# Board.net
KiCad netlist of a schematic drawn in EAGLE
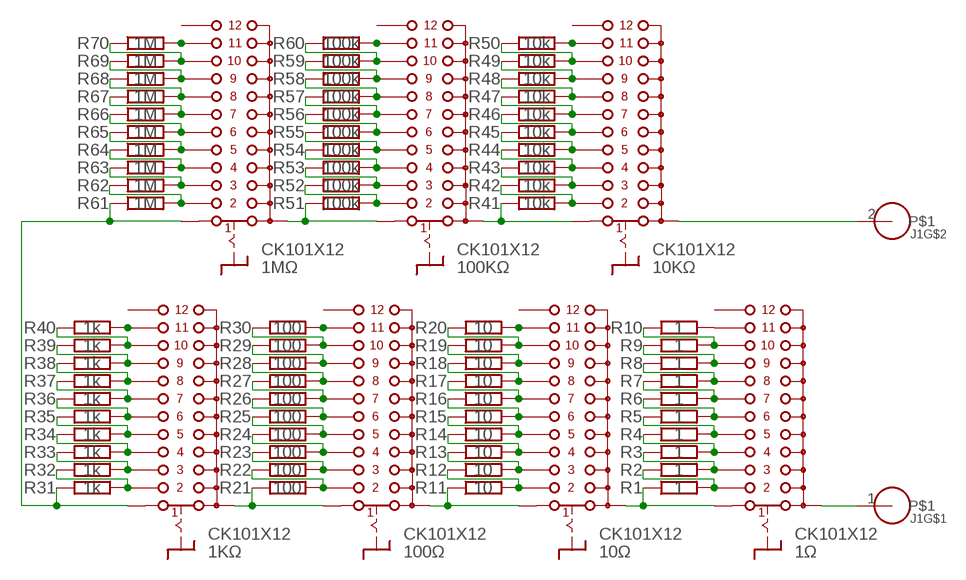
[diagram p0: schematic, sheet 1]

(export (version "E")
  (design (tool "Eeschema 10.0.6"))
  (components
    (comp (ref "1KΩ")
      (value "CK101X12")
      (footprint "eagle-import:CK101X12")
      (libsource (lib "eagle-import") (part "CK101X12"))
    )
    (comp (ref "1MΩ")
      (value "CK101X12")
      (footprint "eagle-import:CK101X12")
      (libsource (lib "eagle-import") (part "CK101X12"))
    )
    (comp (ref "1Ω")
      (value "CK101X12")
      (footprint "eagle-import:CK101X12")
      (libsource (lib "eagle-import") (part "CK101X12"))
    )
    (comp (ref "10KΩ")
      (value "CK101X12")
      (footprint "eagle-import:CK101X12")
      (libsource (lib "eagle-import") (part "CK101X12"))
    )
    (comp (ref "10Ω")
      (value "CK101X12")
      (footprint "eagle-import:CK101X12")
      (libsource (lib "eagle-import") (part "CK101X12"))
    )
    (comp (ref "100KΩ")
      (value "CK101X12")
      (footprint "eagle-import:CK101X12")
      (libsource (lib "eagle-import") (part "CK101X12"))
    )
    (comp (ref "100Ω")
      (value "CK101X12")
      (footprint "eagle-import:CK101X12")
      (libsource (lib "eagle-import") (part "CK101X12"))
    )
    (comp (ref "J1")
      (value "MOLEX-1X2")
      (footprint "eagle-import:MOLEX-1X2_LOCK")
      (libsource (lib "eagle-import") (part "MOLEX-1X2"))
    )
    (comp (ref "R1")
      (value "1")
      (footprint "eagle-import:0207_2V")
      (libsource (lib "eagle-import") (part "R-EU"))
    )
    (comp (ref "R2")
      (value "1")
      (footprint "eagle-import:0207_2V")
      (libsource (lib "eagle-import") (part "R-EU"))
    )
    (comp (ref "R3")
      (value "1")
      (footprint "eagle-import:0207_2V")
      (libsource (lib "eagle-import") (part "R-EU"))
    )
    (comp (ref "R4")
      (value "1")
      (footprint "eagle-import:0207_2V")
      (libsource (lib "eagle-import") (part "R-EU"))
    )
    (comp (ref "R5")
      (value "1")
      (footprint "eagle-import:0207_2V")
      (libsource (lib "eagle-import") (part "R-EU"))
    )
    (comp (ref "R6")
      (value "1")
      (footprint "eagle-import:0207_2V")
      (libsource (lib "eagle-import") (part "R-EU"))
    )
    (comp (ref "R7")
      (value "1")
      (footprint "eagle-import:0207_2V")
      (libsource (lib "eagle-import") (part "R-EU"))
    )
    (comp (ref "R8")
      (value "1")
      (footprint "eagle-import:0207_2V")
      (libsource (lib "eagle-import") (part "R-EU"))
    )
    (comp (ref "R9")
      (value "1")
      (footprint "eagle-import:0207_2V")
      (libsource (lib "eagle-import") (part "R-EU"))
    )
    (comp (ref "R10")
      (value "1")
      (footprint "eagle-import:0207_2V")
      (libsource (lib "eagle-import") (part "R-EU"))
    )
    (comp (ref "R11")
      (value "10")
      (footprint "eagle-import:0207_2V")
      (libsource (lib "eagle-import") (part "R-EU"))
    )
    (comp (ref "R12")
      (value "10")
      (footprint "eagle-import:0207_2V")
      (libsource (lib "eagle-import") (part "R-EU"))
    )
    (comp (ref "R13")
      (value "10")
      (footprint "eagle-import:0207_2V")
      (libsource (lib "eagle-import") (part "R-EU"))
    )
    (comp (ref "R14")
      (value "10")
      (footprint "eagle-import:0207_2V")
      (libsource (lib "eagle-import") (part "R-EU"))
    )
    (comp (ref "R15")
      (value "10")
      (footprint "eagle-import:0207_2V")
      (libsource (lib "eagle-import") (part "R-EU"))
    )
    (comp (ref "R16")
      (value "10")
      (footprint "eagle-import:0207_2V")
      (libsource (lib "eagle-import") (part "R-EU"))
    )
    (comp (ref "R17")
      (value "10")
      (footprint "eagle-import:0207_2V")
      (libsource (lib "eagle-import") (part "R-EU"))
    )
    (comp (ref "R18")
      (value "10")
      (footprint "eagle-import:0207_2V")
      (libsource (lib "eagle-import") (part "R-EU"))
    )
    (comp (ref "R19")
      (value "10")
      (footprint "eagle-import:0207_2V")
      (libsource (lib "eagle-import") (part "R-EU"))
    )
    (comp (ref "R20")
      (value "10")
      (footprint "eagle-import:0207_2V")
      (libsource (lib "eagle-import") (part "R-EU"))
    )
    (comp (ref "R21")
      (value "100")
      (footprint "eagle-import:0207_2V")
      (libsource (lib "eagle-import") (part "R-EU"))
    )
    (comp (ref "R22")
      (value "100")
      (footprint "eagle-import:0207_2V")
      (libsource (lib "eagle-import") (part "R-EU"))
    )
    (comp (ref "R23")
      (value "100")
      (footprint "eagle-import:0207_2V")
      (libsource (lib "eagle-import") (part "R-EU"))
    )
    (comp (ref "R24")
      (value "100")
      (footprint "eagle-import:0207_2V")
      (libsource (lib "eagle-import") (part "R-EU"))
    )
    (comp (ref "R25")
      (value "100")
      (footprint "eagle-import:0207_2V")
      (libsource (lib "eagle-import") (part "R-EU"))
    )
    (comp (ref "R26")
      (value "100")
      (footprint "eagle-import:0207_2V")
      (libsource (lib "eagle-import") (part "R-EU"))
    )
    (comp (ref "R27")
      (value "100")
      (footprint "eagle-import:0207_2V")
      (libsource (lib "eagle-import") (part "R-EU"))
    )
    (comp (ref "R28")
      (value "100")
      (footprint "eagle-import:0207_2V")
      (libsource (lib "eagle-import") (part "R-EU"))
    )
    (comp (ref "R29")
      (value "100")
      (footprint "eagle-import:0207_2V")
      (libsource (lib "eagle-import") (part "R-EU"))
    )
    (comp (ref "R30")
      (value "100")
      (footprint "eagle-import:0207_2V")
      (libsource (lib "eagle-import") (part "R-EU"))
    )
    (comp (ref "R31")
      (value "1k")
      (footprint "eagle-import:0207_2V")
      (libsource (lib "eagle-import") (part "R-EU"))
    )
    (comp (ref "R32")
      (value "1k")
      (footprint "eagle-import:0207_2V")
      (libsource (lib "eagle-import") (part "R-EU"))
    )
    (comp (ref "R33")
      (value "1k")
      (footprint "eagle-import:0207_2V")
      (libsource (lib "eagle-import") (part "R-EU"))
    )
    (comp (ref "R34")
      (value "1k")
      (footprint "eagle-import:0207_2V")
      (libsource (lib "eagle-import") (part "R-EU"))
    )
    (comp (ref "R35")
      (value "1k")
      (footprint "eagle-import:0207_2V")
      (libsource (lib "eagle-import") (part "R-EU"))
    )
    (comp (ref "R36")
      (value "1k")
      (footprint "eagle-import:0207_2V")
      (libsource (lib "eagle-import") (part "R-EU"))
    )
    (comp (ref "R37")
      (value "1k")
      (footprint "eagle-import:0207_2V")
      (libsource (lib "eagle-import") (part "R-EU"))
    )
    (comp (ref "R38")
      (value "1k")
      (footprint "eagle-import:0207_2V")
      (libsource (lib "eagle-import") (part "R-EU"))
    )
    (comp (ref "R39")
      (value "1k")
      (footprint "eagle-import:0207_2V")
      (libsource (lib "eagle-import") (part "R-EU"))
    )
    (comp (ref "R40")
      (value "1k")
      (footprint "eagle-import:0207_2V")
      (libsource (lib "eagle-import") (part "R-EU"))
    )
    (comp (ref "R41")
      (value "10k")
      (footprint "eagle-import:0207_2V")
      (libsource (lib "eagle-import") (part "R-EU"))
    )
    (comp (ref "R42")
      (value "10k")
      (footprint "eagle-import:0207_2V")
      (libsource (lib "eagle-import") (part "R-EU"))
    )
    (comp (ref "R43")
      (value "10k")
      (footprint "eagle-import:0207_2V")
      (libsource (lib "eagle-import") (part "R-EU"))
    )
    (comp (ref "R44")
      (value "10k")
      (footprint "eagle-import:0207_2V")
      (libsource (lib "eagle-import") (part "R-EU"))
    )
    (comp (ref "R45")
      (value "10k")
      (footprint "eagle-import:0207_2V")
      (libsource (lib "eagle-import") (part "R-EU"))
    )
    (comp (ref "R46")
      (value "10k")
      (footprint "eagle-import:0207_2V")
      (libsource (lib "eagle-import") (part "R-EU"))
    )
    (comp (ref "R47")
      (value "10k")
      (footprint "eagle-import:0207_2V")
      (libsource (lib "eagle-import") (part "R-EU"))
    )
    (comp (ref "R48")
      (value "10k")
      (footprint "eagle-import:0207_2V")
      (libsource (lib "eagle-import") (part "R-EU"))
    )
    (comp (ref "R49")
      (value "10k")
      (footprint "eagle-import:0207_2V")
      (libsource (lib "eagle-import") (part "R-EU"))
    )
    (comp (ref "R50")
      (value "10k")
      (footprint "eagle-import:0207_2V")
      (libsource (lib "eagle-import") (part "R-EU"))
    )
    (comp (ref "R51")
      (value "100k")
      (footprint "eagle-import:0207_2V")
      (libsource (lib "eagle-import") (part "R-EU"))
    )
    (comp (ref "R52")
      (value "100k")
      (footprint "eagle-import:0207_2V")
      (libsource (lib "eagle-import") (part "R-EU"))
    )
    (comp (ref "R53")
      (value "100k")
      (footprint "eagle-import:0207_2V")
      (libsource (lib "eagle-import") (part "R-EU"))
    )
    (comp (ref "R54")
      (value "100k")
      (footprint "eagle-import:0207_2V")
      (libsource (lib "eagle-import") (part "R-EU"))
    )
    (comp (ref "R55")
      (value "100k")
      (footprint "eagle-import:0207_2V")
      (libsource (lib "eagle-import") (part "R-EU"))
    )
    (comp (ref "R56")
      (value "100k")
      (footprint "eagle-import:0207_2V")
      (libsource (lib "eagle-import") (part "R-EU"))
    )
    (comp (ref "R57")
      (value "100k")
      (footprint "eagle-import:0207_2V")
      (libsource (lib "eagle-import") (part "R-EU"))
    )
    (comp (ref "R58")
      (value "100k")
      (footprint "eagle-import:0207_2V")
      (libsource (lib "eagle-import") (part "R-EU"))
    )
    (comp (ref "R59")
      (value "100k")
      (footprint "eagle-import:0207_2V")
      (libsource (lib "eagle-import") (part "R-EU"))
    )
    (comp (ref "R60")
      (value "100k")
      (footprint "eagle-import:0207_2V")
      (libsource (lib "eagle-import") (part "R-EU"))
    )
    (comp (ref "R61")
      (value "1M")
      (footprint "eagle-import:0207_2V")
      (libsource (lib "eagle-import") (part "R-EU"))
    )
    (comp (ref "R62")
      (value "1M")
      (footprint "eagle-import:0207_2V")
      (libsource (lib "eagle-import") (part "R-EU"))
    )
    (comp (ref "R63")
      (value "1M")
      (footprint "eagle-import:0207_2V")
      (libsource (lib "eagle-import") (part "R-EU"))
    )
    (comp (ref "R64")
      (value "1M")
      (footprint "eagle-import:0207_2V")
      (libsource (lib "eagle-import") (part "R-EU"))
    )
    (comp (ref "R65")
      (value "1M")
      (footprint "eagle-import:0207_2V")
      (libsource (lib "eagle-import") (part "R-EU"))
    )
    (comp (ref "R66")
      (value "1M")
      (footprint "eagle-import:0207_2V")
      (libsource (lib "eagle-import") (part "R-EU"))
    )
    (comp (ref "R67")
      (value "1M")
      (footprint "eagle-import:0207_2V")
      (libsource (lib "eagle-import") (part "R-EU"))
    )
    (comp (ref "R68")
      (value "1M")
      (footprint "eagle-import:0207_2V")
      (libsource (lib "eagle-import") (part "R-EU"))
    )
    (comp (ref "R69")
      (value "1M")
      (footprint "eagle-import:0207_2V")
      (libsource (lib "eagle-import") (part "R-EU"))
    )
    (comp (ref "R70")
      (value "1M")
      (footprint "eagle-import:0207_2V")
      (libsource (lib "eagle-import") (part "R-EU"))
    )
  )
  (nets
    (net (code "1") (name "Net-(1KΩ-Pad1)") (class "Default")
      (node (ref "1KΩ") (pin "1") (pinfunction "1_1") (pintype "passive"))
      (node (ref "1MΩ") (pin "1") (pinfunction "1_1") (pintype "passive"))
      (node (ref "R31") (pin "1") (pinfunction "1_1") (pintype "passive"))
      (node (ref "R61") (pin "1") (pinfunction "1_1") (pintype "passive"))
    )
    (net (code "2") (name "Net-(1KΩ-Pad2)") (class "Default")
      (node (ref "1KΩ") (pin "2") (pinfunction "2_2") (pintype "passive"))
      (node (ref "R31") (pin "2") (pinfunction "2_2") (pintype "passive"))
      (node (ref "R32") (pin "1") (pinfunction "1_1") (pintype "passive"))
    )
    (net (code "3") (name "Net-(1KΩ-Pad3)") (class "Default")
      (node (ref "1KΩ") (pin "3") (pinfunction "3_3") (pintype "passive"))
      (node (ref "R32") (pin "2") (pinfunction "2_2") (pintype "passive"))
      (node (ref "R33") (pin "1") (pinfunction "1_1") (pintype "passive"))
    )
    (net (code "4") (name "Net-(1KΩ-Pad4)") (class "Default")
      (node (ref "1KΩ") (pin "4") (pinfunction "4_4") (pintype "passive"))
      (node (ref "R33") (pin "2") (pinfunction "2_2") (pintype "passive"))
      (node (ref "R34") (pin "1") (pinfunction "1_1") (pintype "passive"))
    )
    (net (code "5") (name "Net-(1KΩ-Pad5)") (class "Default")
      (node (ref "1KΩ") (pin "5") (pinfunction "5_5") (pintype "passive"))
      (node (ref "R34") (pin "2") (pinfunction "2_2") (pintype "passive"))
      (node (ref "R35") (pin "1") (pinfunction "1_1") (pintype "passive"))
    )
    (net (code "6") (name "Net-(1KΩ-Pad6)") (class "Default")
      (node (ref "1KΩ") (pin "6") (pinfunction "6_6") (pintype "passive"))
      (node (ref "R35") (pin "2") (pinfunction "2_2") (pintype "passive"))
      (node (ref "R36") (pin "1") (pinfunction "1_1") (pintype "passive"))
    )
    (net (code "7") (name "Net-(1KΩ-Pad7)") (class "Default")
      (node (ref "1KΩ") (pin "7") (pinfunction "7_7") (pintype "passive"))
      (node (ref "R36") (pin "2") (pinfunction "2_2") (pintype "passive"))
      (node (ref "R37") (pin "1") (pinfunction "1_1") (pintype "passive"))
    )
    (net (code "8") (name "Net-(1KΩ-Pad8)") (class "Default")
      (node (ref "1KΩ") (pin "8") (pinfunction "8_8") (pintype "passive"))
      (node (ref "R37") (pin "2") (pinfunction "2_2") (pintype "passive"))
      (node (ref "R38") (pin "1") (pinfunction "1_1") (pintype "passive"))
    )
    (net (code "9") (name "Net-(1KΩ-Pad9)") (class "Default")
      (node (ref "1KΩ") (pin "9") (pinfunction "9_9") (pintype "passive"))
      (node (ref "R38") (pin "2") (pinfunction "2_2") (pintype "passive"))
      (node (ref "R39") (pin "1") (pinfunction "1_1") (pintype "passive"))
    )
    (net (code "10") (name "Net-(1KΩ-Pad10)") (class "Default")
      (node (ref "1KΩ") (pin "10") (pinfunction "10_10") (pintype "passive"))
      (node (ref "R39") (pin "2") (pinfunction "2_2") (pintype "passive"))
      (node (ref "R40") (pin "1") (pinfunction "1_1") (pintype "passive"))
    )
    (net (code "11") (name "Net-(1KΩ-Pad11)") (class "Default")
      (node (ref "1KΩ") (pin "11") (pinfunction "11_11") (pintype "passive"))
      (node (ref "R40") (pin "2") (pinfunction "2_2") (pintype "passive"))
    )
    (net (code "12") (name "Net-(1MΩ-Pad2)") (class "Default")
      (node (ref "1MΩ") (pin "2") (pinfunction "2_2") (pintype "passive"))
      (node (ref "R61") (pin "2") (pinfunction "2_2") (pintype "passive"))
      (node (ref "R62") (pin "1") (pinfunction "1_1") (pintype "passive"))
    )
    (net (code "13") (name "Net-(1MΩ-Pad3)") (class "Default")
      (node (ref "1MΩ") (pin "3") (pinfunction "3_3") (pintype "passive"))
      (node (ref "R62") (pin "2") (pinfunction "2_2") (pintype "passive"))
      (node (ref "R63") (pin "1") (pinfunction "1_1") (pintype "passive"))
    )
    (net (code "14") (name "Net-(1MΩ-Pad4)") (class "Default")
      (node (ref "1MΩ") (pin "4") (pinfunction "4_4") (pintype "passive"))
      (node (ref "R63") (pin "2") (pinfunction "2_2") (pintype "passive"))
      (node (ref "R64") (pin "1") (pinfunction "1_1") (pintype "passive"))
    )
    (net (code "15") (name "Net-(1MΩ-Pad5)") (class "Default")
      (node (ref "1MΩ") (pin "5") (pinfunction "5_5") (pintype "passive"))
      (node (ref "R64") (pin "2") (pinfunction "2_2") (pintype "passive"))
      (node (ref "R65") (pin "1") (pinfunction "1_1") (pintype "passive"))
    )
    (net (code "16") (name "Net-(1MΩ-Pad6)") (class "Default")
      (node (ref "1MΩ") (pin "6") (pinfunction "6_6") (pintype "passive"))
      (node (ref "R65") (pin "2") (pinfunction "2_2") (pintype "passive"))
      (node (ref "R66") (pin "1") (pinfunction "1_1") (pintype "passive"))
    )
    (net (code "17") (name "Net-(1MΩ-Pad7)") (class "Default")
      (node (ref "1MΩ") (pin "7") (pinfunction "7_7") (pintype "passive"))
      (node (ref "R66") (pin "2") (pinfunction "2_2") (pintype "passive"))
      (node (ref "R67") (pin "1") (pinfunction "1_1") (pintype "passive"))
    )
    (net (code "18") (name "Net-(1MΩ-Pad8)") (class "Default")
      (node (ref "1MΩ") (pin "8") (pinfunction "8_8") (pintype "passive"))
      (node (ref "R67") (pin "2") (pinfunction "2_2") (pintype "passive"))
      (node (ref "R68") (pin "1") (pinfunction "1_1") (pintype "passive"))
    )
    (net (code "19") (name "Net-(1MΩ-Pad9)") (class "Default")
      (node (ref "1MΩ") (pin "9") (pinfunction "9_9") (pintype "passive"))
      (node (ref "R68") (pin "2") (pinfunction "2_2") (pintype "passive"))
      (node (ref "R69") (pin "1") (pinfunction "1_1") (pintype "passive"))
    )
    (net (code "20") (name "Net-(1MΩ-Pad10)") (class "Default")
      (node (ref "1MΩ") (pin "10") (pinfunction "10_10") (pintype "passive"))
      (node (ref "R69") (pin "2") (pinfunction "2_2") (pintype "passive"))
      (node (ref "R70") (pin "1") (pinfunction "1_1") (pintype "passive"))
    )
    (net (code "21") (name "Net-(1MΩ-Pad11)") (class "Default")
      (node (ref "1MΩ") (pin "11") (pinfunction "11_11") (pintype "passive"))
      (node (ref "R70") (pin "2") (pinfunction "2_2") (pintype "passive"))
    )
    (net (code "22") (name "Net-(1Ω-Pad2)") (class "Default")
      (node (ref "1Ω") (pin "2") (pinfunction "2_2") (pintype "passive"))
      (node (ref "R1") (pin "2") (pinfunction "2_2") (pintype "passive"))
      (node (ref "R2") (pin "1") (pinfunction "1_1") (pintype "passive"))
    )
    (net (code "23") (name "Net-(1Ω-Pad3)") (class "Default")
      (node (ref "1Ω") (pin "3") (pinfunction "3_3") (pintype "passive"))
      (node (ref "R2") (pin "2") (pinfunction "2_2") (pintype "passive"))
      (node (ref "R3") (pin "1") (pinfunction "1_1") (pintype "passive"))
    )
    (net (code "24") (name "Net-(1Ω-Pad4)") (class "Default")
      (node (ref "1Ω") (pin "4") (pinfunction "4_4") (pintype "passive"))
      (node (ref "R3") (pin "2") (pinfunction "2_2") (pintype "passive"))
      (node (ref "R4") (pin "1") (pinfunction "1_1") (pintype "passive"))
    )
    (net (code "25") (name "Net-(1Ω-Pad5)") (class "Default")
      (node (ref "1Ω") (pin "5") (pinfunction "5_5") (pintype "passive"))
      (node (ref "R4") (pin "2") (pinfunction "2_2") (pintype "passive"))
      (node (ref "R5") (pin "1") (pinfunction "1_1") (pintype "passive"))
    )
    (net (code "26") (name "Net-(1Ω-Pad6)") (class "Default")
      (node (ref "1Ω") (pin "6") (pinfunction "6_6") (pintype "passive"))
      (node (ref "R5") (pin "2") (pinfunction "2_2") (pintype "passive"))
      (node (ref "R6") (pin "1") (pinfunction "1_1") (pintype "passive"))
    )
    (net (code "27") (name "Net-(1Ω-Pad7)") (class "Default")
      (node (ref "1Ω") (pin "7") (pinfunction "7_7") (pintype "passive"))
      (node (ref "R6") (pin "2") (pinfunction "2_2") (pintype "passive"))
      (node (ref "R7") (pin "1") (pinfunction "1_1") (pintype "passive"))
    )
    (net (code "28") (name "Net-(1Ω-Pad8)") (class "Default")
      (node (ref "1Ω") (pin "8") (pinfunction "8_8") (pintype "passive"))
      (node (ref "R7") (pin "2") (pinfunction "2_2") (pintype "passive"))
      (node (ref "R8") (pin "1") (pinfunction "1_1") (pintype "passive"))
    )
    (net (code "29") (name "Net-(1Ω-Pad9)") (class "Default")
      (node (ref "1Ω") (pin "9") (pinfunction "9_9") (pintype "passive"))
      (node (ref "R8") (pin "2") (pinfunction "2_2") (pintype "passive"))
      (node (ref "R9") (pin "1") (pinfunction "1_1") (pintype "passive"))
    )
    (net (code "30") (name "Net-(1Ω-Pad10)") (class "Default")
      (node (ref "1Ω") (pin "10") (pinfunction "10_10") (pintype "passive"))
      (node (ref "R10") (pin "1") (pinfunction "1_1") (pintype "passive"))
      (node (ref "R9") (pin "2") (pinfunction "2_2") (pintype "passive"))
    )
    (net (code "31") (name "Net-(1Ω-Pad11)") (class "Default")
      (node (ref "1Ω") (pin "11") (pinfunction "11_11") (pintype "passive"))
      (node (ref "R10") (pin "2") (pinfunction "2_2") (pintype "passive"))
    )
    (net (code "32") (name "Net-(10KΩ-Pad2)") (class "Default")
      (node (ref "10KΩ") (pin "2") (pinfunction "2_2") (pintype "passive"))
      (node (ref "R41") (pin "2") (pinfunction "2_2") (pintype "passive"))
      (node (ref "R42") (pin "1") (pinfunction "1_1") (pintype "passive"))
    )
    (net (code "33") (name "Net-(10KΩ-Pad3)") (class "Default")
      (node (ref "10KΩ") (pin "3") (pinfunction "3_3") (pintype "passive"))
      (node (ref "R42") (pin "2") (pinfunction "2_2") (pintype "passive"))
      (node (ref "R43") (pin "1") (pinfunction "1_1") (pintype "passive"))
    )
    (net (code "34") (name "Net-(10KΩ-Pad4)") (class "Default")
      (node (ref "10KΩ") (pin "4") (pinfunction "4_4") (pintype "passive"))
      (node (ref "R43") (pin "2") (pinfunction "2_2") (pintype "passive"))
      (node (ref "R44") (pin "1") (pinfunction "1_1") (pintype "passive"))
    )
    (net (code "35") (name "Net-(10KΩ-Pad5)") (class "Default")
      (node (ref "10KΩ") (pin "5") (pinfunction "5_5") (pintype "passive"))
      (node (ref "R44") (pin "2") (pinfunction "2_2") (pintype "passive"))
      (node (ref "R45") (pin "1") (pinfunction "1_1") (pintype "passive"))
    )
    (net (code "36") (name "Net-(10KΩ-Pad6)") (class "Default")
      (node (ref "10KΩ") (pin "6") (pinfunction "6_6") (pintype "passive"))
      (node (ref "R45") (pin "2") (pinfunction "2_2") (pintype "passive"))
      (node (ref "R46") (pin "1") (pinfunction "1_1") (pintype "passive"))
    )
    (net (code "37") (name "Net-(10KΩ-Pad7)") (class "Default")
      (node (ref "10KΩ") (pin "7") (pinfunction "7_7") (pintype "passive"))
      (node (ref "R46") (pin "2") (pinfunction "2_2") (pintype "passive"))
      (node (ref "R47") (pin "1") (pinfunction "1_1") (pintype "passive"))
    )
    (net (code "38") (name "Net-(10KΩ-Pad8)") (class "Default")
      (node (ref "10KΩ") (pin "8") (pinfunction "8_8") (pintype "passive"))
      (node (ref "R47") (pin "2") (pinfunction "2_2") (pintype "passive"))
      (node (ref "R48") (pin "1") (pinfunction "1_1") (pintype "passive"))
    )
    (net (code "39") (name "Net-(10KΩ-Pad9)") (class "Default")
      (node (ref "10KΩ") (pin "9") (pinfunction "9_9") (pintype "passive"))
      (node (ref "R48") (pin "2") (pinfunction "2_2") (pintype "passive"))
      (node (ref "R49") (pin "1") (pinfunction "1_1") (pintype "passive"))
    )
    (net (code "40") (name "Net-(10KΩ-Pad10)") (class "Default")
      (node (ref "10KΩ") (pin "10") (pinfunction "10_10") (pintype "passive"))
      (node (ref "R49") (pin "2") (pinfunction "2_2") (pintype "passive"))
      (node (ref "R50") (pin "1") (pinfunction "1_1") (pintype "passive"))
    )
    (net (code "41") (name "Net-(10KΩ-Pad11)") (class "Default")
      (node (ref "10KΩ") (pin "11") (pinfunction "11_11") (pintype "passive"))
      (node (ref "R50") (pin "2") (pinfunction "2_2") (pintype "passive"))
    )
    (net (code "42") (name "Net-(10Ω-Pad2)") (class "Default")
      (node (ref "10Ω") (pin "2") (pinfunction "2_2") (pintype "passive"))
      (node (ref "R11") (pin "2") (pinfunction "2_2") (pintype "passive"))
      (node (ref "R12") (pin "1") (pinfunction "1_1") (pintype "passive"))
    )
    (net (code "43") (name "Net-(10Ω-Pad3)") (class "Default")
      (node (ref "10Ω") (pin "3") (pinfunction "3_3") (pintype "passive"))
      (node (ref "R12") (pin "2") (pinfunction "2_2") (pintype "passive"))
      (node (ref "R13") (pin "1") (pinfunction "1_1") (pintype "passive"))
    )
    (net (code "44") (name "Net-(10Ω-Pad4)") (class "Default")
      (node (ref "10Ω") (pin "4") (pinfunction "4_4") (pintype "passive"))
      (node (ref "R13") (pin "2") (pinfunction "2_2") (pintype "passive"))
      (node (ref "R14") (pin "1") (pinfunction "1_1") (pintype "passive"))
    )
    (net (code "45") (name "Net-(10Ω-Pad5)") (class "Default")
      (node (ref "10Ω") (pin "5") (pinfunction "5_5") (pintype "passive"))
      (node (ref "R14") (pin "2") (pinfunction "2_2") (pintype "passive"))
      (node (ref "R15") (pin "1") (pinfunction "1_1") (pintype "passive"))
    )
    (net (code "46") (name "Net-(10Ω-Pad6)") (class "Default")
      (node (ref "10Ω") (pin "6") (pinfunction "6_6") (pintype "passive"))
      (node (ref "R15") (pin "2") (pinfunction "2_2") (pintype "passive"))
      (node (ref "R16") (pin "1") (pinfunction "1_1") (pintype "passive"))
    )
    (net (code "47") (name "Net-(10Ω-Pad7)") (class "Default")
      (node (ref "10Ω") (pin "7") (pinfunction "7_7") (pintype "passive"))
      (node (ref "R16") (pin "2") (pinfunction "2_2") (pintype "passive"))
      (node (ref "R17") (pin "1") (pinfunction "1_1") (pintype "passive"))
    )
    (net (code "48") (name "Net-(10Ω-Pad8)") (class "Default")
      (node (ref "10Ω") (pin "8") (pinfunction "8_8") (pintype "passive"))
      (node (ref "R17") (pin "2") (pinfunction "2_2") (pintype "passive"))
      (node (ref "R18") (pin "1") (pinfunction "1_1") (pintype "passive"))
    )
    (net (code "49") (name "Net-(10Ω-Pad9)") (class "Default")
      (node (ref "10Ω") (pin "9") (pinfunction "9_9") (pintype "passive"))
      (node (ref "R18") (pin "2") (pinfunction "2_2") (pintype "passive"))
      (node (ref "R19") (pin "1") (pinfunction "1_1") (pintype "passive"))
    )
    (net (code "50") (name "Net-(10Ω-Pad10)") (class "Default")
      (node (ref "10Ω") (pin "10") (pinfunction "10_10") (pintype "passive"))
      (node (ref "R19") (pin "2") (pinfunction "2_2") (pintype "passive"))
      (node (ref "R20") (pin "1") (pinfunction "1_1") (pintype "passive"))
    )
    (net (code "51") (name "Net-(10Ω-Pad11)") (class "Default")
      (node (ref "10Ω") (pin "11") (pinfunction "11_11") (pintype "passive"))
      (node (ref "R20") (pin "2") (pinfunction "2_2") (pintype "passive"))
    )
    (net (code "52") (name "Net-(10Ω-PadA)") (class "Default")
      (node (ref "10Ω") (pin "A") (pinfunction "A_A") (pintype "passive"))
      (node (ref "1Ω") (pin "1") (pinfunction "1_1") (pintype "passive"))
      (node (ref "R1") (pin "1") (pinfunction "1_1") (pintype "passive"))
    )
    (net (code "53") (name "Net-(100KΩ-Pad1)") (class "Default")
      (node (ref "100KΩ") (pin "1") (pinfunction "1_1") (pintype "passive"))
      (node (ref "1MΩ") (pin "A") (pinfunction "A_A") (pintype "passive"))
      (node (ref "R51") (pin "1") (pinfunction "1_1") (pintype "passive"))
    )
    (net (code "54") (name "Net-(100KΩ-Pad2)") (class "Default")
      (node (ref "100KΩ") (pin "2") (pinfunction "2_2") (pintype "passive"))
      (node (ref "R51") (pin "2") (pinfunction "2_2") (pintype "passive"))
      (node (ref "R52") (pin "1") (pinfunction "1_1") (pintype "passive"))
    )
    (net (code "55") (name "Net-(100KΩ-Pad3)") (class "Default")
      (node (ref "100KΩ") (pin "3") (pinfunction "3_3") (pintype "passive"))
      (node (ref "R52") (pin "2") (pinfunction "2_2") (pintype "passive"))
      (node (ref "R53") (pin "1") (pinfunction "1_1") (pintype "passive"))
    )
    (net (code "56") (name "Net-(100KΩ-Pad4)") (class "Default")
      (node (ref "100KΩ") (pin "4") (pinfunction "4_4") (pintype "passive"))
      (node (ref "R53") (pin "2") (pinfunction "2_2") (pintype "passive"))
      (node (ref "R54") (pin "1") (pinfunction "1_1") (pintype "passive"))
    )
    (net (code "57") (name "Net-(100KΩ-Pad5)") (class "Default")
      (node (ref "100KΩ") (pin "5") (pinfunction "5_5") (pintype "passive"))
      (node (ref "R54") (pin "2") (pinfunction "2_2") (pintype "passive"))
      (node (ref "R55") (pin "1") (pinfunction "1_1") (pintype "passive"))
    )
    (net (code "58") (name "Net-(100KΩ-Pad6)") (class "Default")
      (node (ref "100KΩ") (pin "6") (pinfunction "6_6") (pintype "passive"))
      (node (ref "R55") (pin "2") (pinfunction "2_2") (pintype "passive"))
      (node (ref "R56") (pin "1") (pinfunction "1_1") (pintype "passive"))
    )
    (net (code "59") (name "Net-(100KΩ-Pad7)") (class "Default")
      (node (ref "100KΩ") (pin "7") (pinfunction "7_7") (pintype "passive"))
      (node (ref "R56") (pin "2") (pinfunction "2_2") (pintype "passive"))
      (node (ref "R57") (pin "1") (pinfunction "1_1") (pintype "passive"))
    )
    (net (code "60") (name "Net-(100KΩ-Pad8)") (class "Default")
      (node (ref "100KΩ") (pin "8") (pinfunction "8_8") (pintype "passive"))
      (node (ref "R57") (pin "2") (pinfunction "2_2") (pintype "passive"))
      (node (ref "R58") (pin "1") (pinfunction "1_1") (pintype "passive"))
    )
    (net (code "61") (name "Net-(100KΩ-Pad9)") (class "Default")
      (node (ref "100KΩ") (pin "9") (pinfunction "9_9") (pintype "passive"))
      (node (ref "R58") (pin "2") (pinfunction "2_2") (pintype "passive"))
      (node (ref "R59") (pin "1") (pinfunction "1_1") (pintype "passive"))
    )
    (net (code "62") (name "Net-(100KΩ-Pad10)") (class "Default")
      (node (ref "100KΩ") (pin "10") (pinfunction "10_10") (pintype "passive"))
      (node (ref "R59") (pin "2") (pinfunction "2_2") (pintype "passive"))
      (node (ref "R60") (pin "1") (pinfunction "1_1") (pintype "passive"))
    )
    (net (code "63") (name "Net-(100KΩ-Pad11)") (class "Default")
      (node (ref "100KΩ") (pin "11") (pinfunction "11_11") (pintype "passive"))
      (node (ref "R60") (pin "2") (pinfunction "2_2") (pintype "passive"))
    )
    (net (code "64") (name "Net-(100KΩ-PadA)") (class "Default")
      (node (ref "100KΩ") (pin "A") (pinfunction "A_A") (pintype "passive"))
      (node (ref "10KΩ") (pin "1") (pinfunction "1_1") (pintype "passive"))
      (node (ref "R41") (pin "1") (pinfunction "1_1") (pintype "passive"))
    )
    (net (code "65") (name "Net-(100Ω-Pad1)") (class "Default")
      (node (ref "100Ω") (pin "1") (pinfunction "1_1") (pintype "passive"))
      (node (ref "1KΩ") (pin "A") (pinfunction "A_A") (pintype "passive"))
      (node (ref "R21") (pin "1") (pinfunction "1_1") (pintype "passive"))
    )
    (net (code "66") (name "Net-(100Ω-Pad2)") (class "Default")
      (node (ref "100Ω") (pin "2") (pinfunction "2_2") (pintype "passive"))
      (node (ref "R21") (pin "2") (pinfunction "2_2") (pintype "passive"))
      (node (ref "R22") (pin "1") (pinfunction "1_1") (pintype "passive"))
    )
    (net (code "67") (name "Net-(100Ω-Pad3)") (class "Default")
      (node (ref "100Ω") (pin "3") (pinfunction "3_3") (pintype "passive"))
      (node (ref "R22") (pin "2") (pinfunction "2_2") (pintype "passive"))
      (node (ref "R23") (pin "1") (pinfunction "1_1") (pintype "passive"))
    )
    (net (code "68") (name "Net-(100Ω-Pad4)") (class "Default")
      (node (ref "100Ω") (pin "4") (pinfunction "4_4") (pintype "passive"))
      (node (ref "R23") (pin "2") (pinfunction "2_2") (pintype "passive"))
      (node (ref "R24") (pin "1") (pinfunction "1_1") (pintype "passive"))
    )
    (net (code "69") (name "Net-(100Ω-Pad5)") (class "Default")
      (node (ref "100Ω") (pin "5") (pinfunction "5_5") (pintype "passive"))
      (node (ref "R24") (pin "2") (pinfunction "2_2") (pintype "passive"))
      (node (ref "R25") (pin "1") (pinfunction "1_1") (pintype "passive"))
    )
    (net (code "70") (name "Net-(100Ω-Pad6)") (class "Default")
      (node (ref "100Ω") (pin "6") (pinfunction "6_6") (pintype "passive"))
      (node (ref "R25") (pin "2") (pinfunction "2_2") (pintype "passive"))
      (node (ref "R26") (pin "1") (pinfunction "1_1") (pintype "passive"))
    )
    (net (code "71") (name "Net-(100Ω-Pad7)") (class "Default")
      (node (ref "100Ω") (pin "7") (pinfunction "7_7") (pintype "passive"))
      (node (ref "R26") (pin "2") (pinfunction "2_2") (pintype "passive"))
      (node (ref "R27") (pin "1") (pinfunction "1_1") (pintype "passive"))
    )
    (net (code "72") (name "Net-(100Ω-Pad8)") (class "Default")
      (node (ref "100Ω") (pin "8") (pinfunction "8_8") (pintype "passive"))
      (node (ref "R27") (pin "2") (pinfunction "2_2") (pintype "passive"))
      (node (ref "R28") (pin "1") (pinfunction "1_1") (pintype "passive"))
    )
    (net (code "73") (name "Net-(100Ω-Pad9)") (class "Default")
      (node (ref "100Ω") (pin "9") (pinfunction "9_9") (pintype "passive"))
      (node (ref "R28") (pin "2") (pinfunction "2_2") (pintype "passive"))
      (node (ref "R29") (pin "1") (pinfunction "1_1") (pintype "passive"))
    )
    (net (code "74") (name "Net-(100Ω-Pad10)") (class "Default")
      (node (ref "100Ω") (pin "10") (pinfunction "10_10") (pintype "passive"))
      (node (ref "R29") (pin "2") (pinfunction "2_2") (pintype "passive"))
      (node (ref "R30") (pin "1") (pinfunction "1_1") (pintype "passive"))
    )
    (net (code "75") (name "Net-(100Ω-Pad11)") (class "Default")
      (node (ref "100Ω") (pin "11") (pinfunction "11_11") (pintype "passive"))
      (node (ref "R30") (pin "2") (pinfunction "2_2") (pintype "passive"))
    )
    (net (code "76") (name "Net-(100Ω-PadA)") (class "Default")
      (node (ref "100Ω") (pin "A") (pinfunction "A_A") (pintype "passive"))
      (node (ref "10Ω") (pin "1") (pinfunction "1_1") (pintype "passive"))
      (node (ref "R11") (pin "1") (pinfunction "1_1") (pintype "passive"))
    )
    (net (code "77") (name "Net-(J1A-P$1)") (class "Default")
      (node (ref "1Ω") (pin "A") (pinfunction "A_A") (pintype "passive"))
      (node (ref "J1") (pin "1") (pinfunction "P$1_1") (pintype "bidirectional"))
    )
    (net (code "78") (name "Net-(J1B-P$1)") (class "Default")
      (node (ref "10KΩ") (pin "A") (pinfunction "A_A") (pintype "passive"))
      (node (ref "J1") (pin "2") (pinfunction "P$1_2") (pintype "bidirectional"))
    )
    (net (code "79") (name "unconnected-(1KΩ-Pad12)") (class "Default")
      (node (ref "1KΩ") (pin "12") (pinfunction "12_12") (pintype "passive"))
    )
    (net (code "80") (name "unconnected-(1MΩ-Pad12)") (class "Default")
      (node (ref "1MΩ") (pin "12") (pinfunction "12_12") (pintype "passive"))
    )
    (net (code "81") (name "unconnected-(1Ω-Pad12)") (class "Default")
      (node (ref "1Ω") (pin "12") (pinfunction "12_12") (pintype "passive"))
    )
    (net (code "82") (name "unconnected-(10KΩ-Pad12)") (class "Default")
      (node (ref "10KΩ") (pin "12") (pinfunction "12_12") (pintype "passive"))
    )
    (net (code "83") (name "unconnected-(10Ω-Pad12)") (class "Default")
      (node (ref "10Ω") (pin "12") (pinfunction "12_12") (pintype "passive"))
    )
    (net (code "84") (name "unconnected-(100KΩ-Pad12)") (class "Default")
      (node (ref "100KΩ") (pin "12") (pinfunction "12_12") (pintype "passive"))
    )
    (net (code "85") (name "unconnected-(100Ω-Pad12)") (class "Default")
      (node (ref "100Ω") (pin "12") (pinfunction "12_12") (pintype "passive"))
    )
  )
)
